# v1.net
KiCad netlist of a schematic drawn in EAGLE
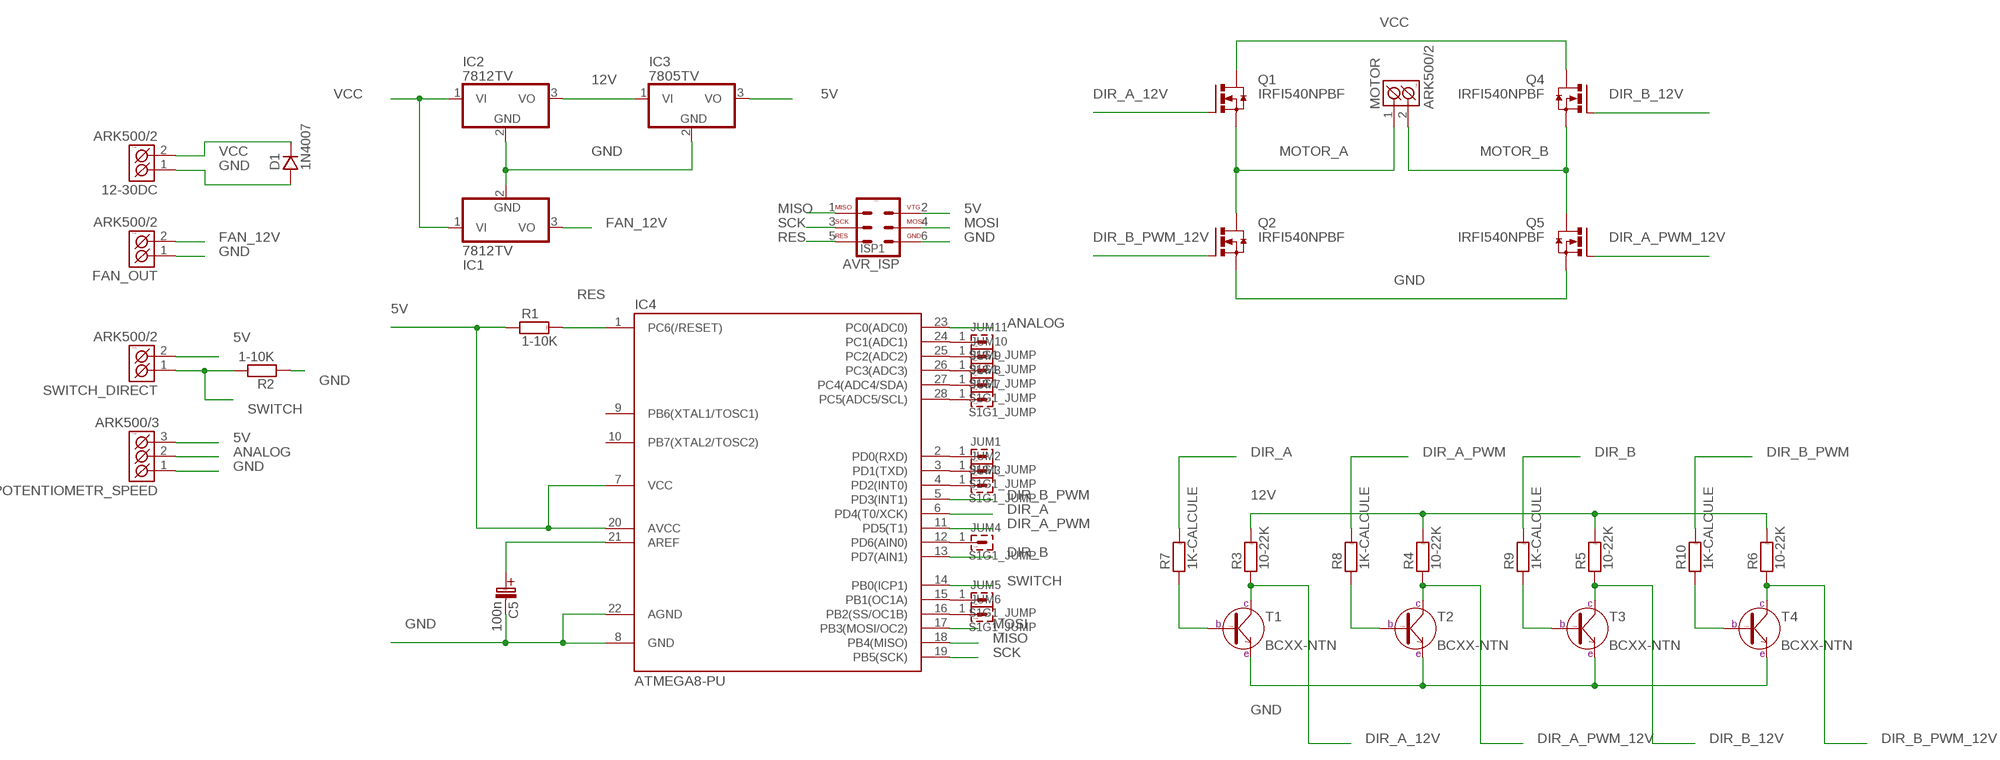
[diagram p0: schematic, sheet 1]

(export (version "E")
  (design (tool "Eeschema 10.0.6"))
  (components
    (comp (ref "12-30DC")
      (value "ARK500/2")
      (footprint "eagle-import:ARK500_2")
      (libsource (lib "eagle-import") (part "ARK500/2"))
    )
    (comp (ref "C5")
      (value "100n")
      (footprint "eagle-import:C-EL_2,5")
      (libsource (lib "eagle-import") (part "C-EL_2,5"))
    )
    (comp (ref "D1")
      (value "1N4007")
      (footprint "eagle-import:DO41")
      (libsource (lib "eagle-import") (part "1N4007"))
    )
    (comp (ref "FAN_OUT")
      (value "ARK500/2")
      (footprint "eagle-import:ARK500_2")
      (libsource (lib "eagle-import") (part "ARK500/2"))
    )
    (comp (ref "IC1")
      (value "7812TV")
      (footprint "eagle-import:TO220V")
      (libsource (lib "eagle-import") (part "78TV12"))
    )
    (comp (ref "IC2")
      (value "7812TV")
      (footprint "eagle-import:TO220V")
      (libsource (lib "eagle-import") (part "78TV12"))
    )
    (comp (ref "IC3")
      (value "7805TV")
      (footprint "eagle-import:TO220V")
      (libsource (lib "eagle-import") (part "78TV05"))
    )
    (comp (ref "IC4")
      (value "ATMEGA8-PU")
      (footprint "eagle-import:DIL28-3")
      (libsource (lib "eagle-import") (part "ATMEGA8-PU"))
    )
    (comp (ref "ISP1")
      (value "AVR_ISP")
      (footprint "eagle-import:MLW06G")
      (libsource (lib "eagle-import") (part "AVR_ISP"))
    )
    (comp (ref "JUM1")
      (value "S1G1_JUMP")
      (footprint "eagle-import:S1G1_JUM")
      (libsource (lib "eagle-import") (part "S1G1_JUMP"))
    )
    (comp (ref "JUM2")
      (value "S1G1_JUMP")
      (footprint "eagle-import:S1G1_JUM")
      (libsource (lib "eagle-import") (part "S1G1_JUMP"))
    )
    (comp (ref "JUM3")
      (value "S1G1_JUMP")
      (footprint "eagle-import:S1G1_JUM")
      (libsource (lib "eagle-import") (part "S1G1_JUMP"))
    )
    (comp (ref "JUM4")
      (value "S1G1_JUMP")
      (footprint "eagle-import:S1G1_JUM")
      (libsource (lib "eagle-import") (part "S1G1_JUMP"))
    )
    (comp (ref "JUM5")
      (value "S1G1_JUMP")
      (footprint "eagle-import:S1G1_JUM")
      (libsource (lib "eagle-import") (part "S1G1_JUMP"))
    )
    (comp (ref "JUM6")
      (value "S1G1_JUMP")
      (footprint "eagle-import:S1G1_JUM")
      (libsource (lib "eagle-import") (part "S1G1_JUMP"))
    )
    (comp (ref "JUM7")
      (value "S1G1_JUMP")
      (footprint "eagle-import:S1G1_JUM")
      (libsource (lib "eagle-import") (part "S1G1_JUMP"))
    )
    (comp (ref "JUM8")
      (value "S1G1_JUMP")
      (footprint "eagle-import:S1G1_JUM")
      (libsource (lib "eagle-import") (part "S1G1_JUMP"))
    )
    (comp (ref "JUM9")
      (value "S1G1_JUMP")
      (footprint "eagle-import:S1G1_JUM")
      (libsource (lib "eagle-import") (part "S1G1_JUMP"))
    )
    (comp (ref "JUM10")
      (value "S1G1_JUMP")
      (footprint "eagle-import:S1G1_JUM")
      (libsource (lib "eagle-import") (part "S1G1_JUMP"))
    )
    (comp (ref "JUM11")
      (value "S1G1_JUMP")
      (footprint "eagle-import:S1G1_JUM")
      (libsource (lib "eagle-import") (part "S1G1_JUMP"))
    )
    (comp (ref "MOTOR")
      (value "ARK500/2")
      (footprint "eagle-import:ARK500_2")
      (libsource (lib "eagle-import") (part "ARK500/2"))
    )
    (comp (ref "POTENTIOMETR_SPEED")
      (value "ARK500/3")
      (footprint "eagle-import:ARK500_3")
      (libsource (lib "eagle-import") (part "ARK500/3"))
    )
    (comp (ref "Q1")
      (value "IRFI540NPBF")
      (footprint "eagle-import:TO220BH")
      (libsource (lib "eagle-import") (part "IRFI540NPBF"))
    )
    (comp (ref "Q2")
      (value "IRFI540NPBF")
      (footprint "eagle-import:TO220BH")
      (libsource (lib "eagle-import") (part "IRFI540NPBF"))
    )
    (comp (ref "Q4")
      (value "IRFI540NPBF")
      (footprint "eagle-import:TO220BH")
      (libsource (lib "eagle-import") (part "IRFI540NPBF"))
    )
    (comp (ref "Q5")
      (value "IRFI540NPBF")
      (footprint "eagle-import:TO220BH")
      (libsource (lib "eagle-import") (part "IRFI540NPBF"))
    )
    (comp (ref "R1")
      (value "1-10K")
      (footprint "eagle-import:R-7,5")
      (libsource (lib "eagle-import") (part "R_7,5"))
    )
    (comp (ref "R2")
      (value "1-10K")
      (footprint "eagle-import:R-7,5")
      (libsource (lib "eagle-import") (part "R_7,5"))
    )
    (comp (ref "R3")
      (value "10-22K")
      (footprint "eagle-import:R-7,5")
      (libsource (lib "eagle-import") (part "R_7,5"))
    )
    (comp (ref "R4")
      (value "10-22K")
      (footprint "eagle-import:R-7,5")
      (libsource (lib "eagle-import") (part "R_7,5"))
    )
    (comp (ref "R5")
      (value "10-22K")
      (footprint "eagle-import:R-7,5")
      (libsource (lib "eagle-import") (part "R_7,5"))
    )
    (comp (ref "R6")
      (value "10-22K")
      (footprint "eagle-import:R-7,5")
      (libsource (lib "eagle-import") (part "R_7,5"))
    )
    (comp (ref "R7")
      (value "1K-CALCULE")
      (footprint "eagle-import:R-7,5")
      (libsource (lib "eagle-import") (part "R_7,5"))
    )
    (comp (ref "R8")
      (value "1K-CALCULE")
      (footprint "eagle-import:R-7,5")
      (libsource (lib "eagle-import") (part "R_7,5"))
    )
    (comp (ref "R9")
      (value "1K-CALCULE")
      (footprint "eagle-import:R-7,5")
      (libsource (lib "eagle-import") (part "R_7,5"))
    )
    (comp (ref "R10")
      (value "1K-CALCULE")
      (footprint "eagle-import:R-7,5")
      (libsource (lib "eagle-import") (part "R_7,5"))
    )
    (comp (ref "SWITCH_DIRECT")
      (value "ARK500/2")
      (footprint "eagle-import:ARK500_2")
      (libsource (lib "eagle-import") (part "ARK500/2"))
    )
    (comp (ref "T1")
      (value "BCXX-NTN")
      (footprint "eagle-import:TO-92")
      (libsource (lib "eagle-import") (part "BC546"))
    )
    (comp (ref "T2")
      (value "BCXX-NTN")
      (footprint "eagle-import:TO-92")
      (libsource (lib "eagle-import") (part "BC546"))
    )
    (comp (ref "T3")
      (value "BCXX-NTN")
      (footprint "eagle-import:TO-92")
      (libsource (lib "eagle-import") (part "BC546"))
    )
    (comp (ref "T4")
      (value "BCXX-NTN")
      (footprint "eagle-import:TO-92")
      (libsource (lib "eagle-import") (part "BC546"))
    )
  )
  (nets
    (net (code "1") (name "/5V") (class "Default")
      (node (ref "IC3") (pin "3") (pinfunction "VO_3") (pintype "passive"))
      (node (ref "IC4") (pin "20") (pinfunction "AVCC_20") (pintype "passive"))
      (node (ref "IC4") (pin "7") (pinfunction "VCC_7") (pintype "power_in"))
      (node (ref "ISP1") (pin "2") (pinfunction "2_2") (pintype "passive"))
      (node (ref "POTENTIOMETR_SPEED") (pin "3") (pinfunction "K3_3") (pintype "passive"))
      (node (ref "R1") (pin "1") (pinfunction "1_1") (pintype "passive"))
      (node (ref "SWITCH_DIRECT") (pin "2") (pinfunction "K2_2") (pintype "passive"))
    )
    (net (code "2") (name "/12V") (class "Default")
      (node (ref "IC2") (pin "3") (pinfunction "VO_3") (pintype "passive"))
      (node (ref "IC3") (pin "1") (pinfunction "VI_1") (pintype "input"))
      (node (ref "R3") (pin "2") (pinfunction "2_2") (pintype "passive"))
      (node (ref "R4") (pin "2") (pinfunction "2_2") (pintype "passive"))
      (node (ref "R5") (pin "2") (pinfunction "2_2") (pintype "passive"))
      (node (ref "R6") (pin "2") (pinfunction "2_2") (pintype "passive"))
    )
    (net (code "3") (name "/ANALOG") (class "Default")
      (node (ref "IC4") (pin "23") (pinfunction "PC0(ADC0)_23") (pintype "bidirectional"))
      (node (ref "POTENTIOMETR_SPEED") (pin "2") (pinfunction "K2_2") (pintype "passive"))
    )
    (net (code "4") (name "/DIR_A") (class "Default")
      (node (ref "IC4") (pin "6") (pinfunction "PD4(T0/XCK)_6") (pintype "bidirectional"))
      (node (ref "R7") (pin "2") (pinfunction "2_2") (pintype "passive"))
    )
    (net (code "5") (name "/DIR_A_12V") (class "Default")
      (node (ref "Q1") (pin "G") (pinfunction "G_G") (pintype "passive"))
      (node (ref "R3") (pin "1") (pinfunction "1_1") (pintype "passive"))
      (node (ref "T1") (pin "1") (pinfunction "C_1") (pintype "passive"))
    )
    (net (code "6") (name "/DIR_A_PWM") (class "Default")
      (node (ref "IC4") (pin "11") (pinfunction "PD5(T1)_11") (pintype "bidirectional"))
      (node (ref "R8") (pin "2") (pinfunction "2_2") (pintype "passive"))
    )
    (net (code "7") (name "/DIR_A_PWM_12V") (class "Default")
      (node (ref "Q5") (pin "G") (pinfunction "G_G") (pintype "passive"))
      (node (ref "R4") (pin "1") (pinfunction "1_1") (pintype "passive"))
      (node (ref "T2") (pin "1") (pinfunction "C_1") (pintype "passive"))
    )
    (net (code "8") (name "/DIR_B") (class "Default")
      (node (ref "IC4") (pin "13") (pinfunction "PD7(AIN1)_13") (pintype "bidirectional"))
      (node (ref "R9") (pin "2") (pinfunction "2_2") (pintype "passive"))
    )
    (net (code "9") (name "/DIR_B_12V") (class "Default")
      (node (ref "Q4") (pin "G") (pinfunction "G_G") (pintype "passive"))
      (node (ref "R5") (pin "1") (pinfunction "1_1") (pintype "passive"))
      (node (ref "T3") (pin "1") (pinfunction "C_1") (pintype "passive"))
    )
    (net (code "10") (name "/DIR_B_PWM") (class "Default")
      (node (ref "IC4") (pin "5") (pinfunction "PD3(INT1)_5") (pintype "bidirectional"))
      (node (ref "R10") (pin "2") (pinfunction "2_2") (pintype "passive"))
    )
    (net (code "11") (name "/DIR_B_PWM_12V") (class "Default")
      (node (ref "Q2") (pin "G") (pinfunction "G_G") (pintype "passive"))
      (node (ref "R6") (pin "1") (pinfunction "1_1") (pintype "passive"))
      (node (ref "T4") (pin "1") (pinfunction "C_1") (pintype "passive"))
    )
    (net (code "12") (name "/FAN_12V") (class "Default")
      (node (ref "FAN_OUT") (pin "2") (pinfunction "K2_2") (pintype "passive"))
      (node (ref "IC1") (pin "3") (pinfunction "VO_3") (pintype "passive"))
    )
    (net (code "13") (name "/GND") (class "Default")
      (node (ref "12-30DC") (pin "1") (pinfunction "K1_1") (pintype "passive"))
      (node (ref "C5") (pin "C-") (pinfunction "C_EL-_C-") (pintype "passive"))
      (node (ref "D1") (pin "A") (pinfunction "A_A") (pintype "passive"))
      (node (ref "FAN_OUT") (pin "1") (pinfunction "K1_1") (pintype "passive"))
      (node (ref "IC1") (pin "2") (pinfunction "GND_2") (pintype "passive"))
      (node (ref "IC2") (pin "2") (pinfunction "GND_2") (pintype "passive"))
      (node (ref "IC3") (pin "2") (pinfunction "GND_2") (pintype "passive"))
      (node (ref "IC4") (pin "22") (pinfunction "AGND_22") (pintype "power_in"))
      (node (ref "IC4") (pin "8") (pinfunction "GND_8") (pintype "power_in"))
      (node (ref "ISP1") (pin "6") (pinfunction "6_6") (pintype "passive"))
      (node (ref "POTENTIOMETR_SPEED") (pin "1") (pinfunction "K1_1") (pintype "passive"))
      (node (ref "Q2") (pin "S") (pinfunction "S_S") (pintype "passive"))
      (node (ref "Q5") (pin "S") (pinfunction "S_S") (pintype "passive"))
      (node (ref "R2") (pin "1") (pinfunction "1_1") (pintype "passive"))
      (node (ref "T1") (pin "3") (pinfunction "E_3") (pintype "passive"))
      (node (ref "T2") (pin "3") (pinfunction "E_3") (pintype "passive"))
      (node (ref "T3") (pin "3") (pinfunction "E_3") (pintype "passive"))
      (node (ref "T4") (pin "3") (pinfunction "E_3") (pintype "passive"))
    )
    (net (code "14") (name "/MISO") (class "Default")
      (node (ref "IC4") (pin "18") (pinfunction "PB4(MISO)_18") (pintype "bidirectional"))
      (node (ref "ISP1") (pin "1") (pinfunction "1_1") (pintype "passive"))
    )
    (net (code "15") (name "/MOSI") (class "Default")
      (node (ref "IC4") (pin "17") (pinfunction "PB3(MOSI/OC2)_17") (pintype "bidirectional"))
      (node (ref "ISP1") (pin "4") (pinfunction "4_4") (pintype "passive"))
    )
    (net (code "16") (name "/MOTOR_A") (class "Default")
      (node (ref "MOTOR") (pin "1") (pinfunction "K1_1") (pintype "passive"))
      (node (ref "Q1") (pin "S") (pinfunction "S_S") (pintype "passive"))
      (node (ref "Q2") (pin "D") (pinfunction "D_D") (pintype "passive"))
    )
    (net (code "17") (name "/MOTOR_B") (class "Default")
      (node (ref "MOTOR") (pin "2") (pinfunction "K2_2") (pintype "passive"))
      (node (ref "Q4") (pin "S") (pinfunction "S_S") (pintype "passive"))
      (node (ref "Q5") (pin "D") (pinfunction "D_D") (pintype "passive"))
    )
    (net (code "18") (name "/RES") (class "Default")
      (node (ref "IC4") (pin "1") (pinfunction "PC6(/RESET)_1") (pintype "bidirectional"))
      (node (ref "ISP1") (pin "5") (pinfunction "5_5") (pintype "passive"))
      (node (ref "R1") (pin "2") (pinfunction "2_2") (pintype "passive"))
    )
    (net (code "19") (name "/SCK") (class "Default")
      (node (ref "IC4") (pin "19") (pinfunction "PB5(SCK)_19") (pintype "bidirectional"))
      (node (ref "ISP1") (pin "3") (pinfunction "3_3") (pintype "passive"))
    )
    (net (code "20") (name "/SWITCH") (class "Default")
      (node (ref "IC4") (pin "14") (pinfunction "PB0(ICP1)_14") (pintype "bidirectional"))
      (node (ref "R2") (pin "2") (pinfunction "2_2") (pintype "passive"))
      (node (ref "SWITCH_DIRECT") (pin "1") (pinfunction "K1_1") (pintype "passive"))
    )
    (net (code "21") (name "/VCC") (class "Default")
      (node (ref "12-30DC") (pin "2") (pinfunction "K2_2") (pintype "passive"))
      (node (ref "D1") (pin "K") (pinfunction "K_K") (pintype "passive"))
      (node (ref "IC1") (pin "1") (pinfunction "VI_1") (pintype "input"))
      (node (ref "IC2") (pin "1") (pinfunction "VI_1") (pintype "input"))
      (node (ref "Q1") (pin "D") (pinfunction "D_D") (pintype "passive"))
      (node (ref "Q4") (pin "D") (pinfunction "D_D") (pintype "passive"))
    )
    (net (code "22") (name "Net-(C5-C_EL+)") (class "Default")
      (node (ref "C5") (pin "C+") (pinfunction "C_EL+_C+") (pintype "passive"))
      (node (ref "IC4") (pin "21") (pinfunction "AREF_21") (pintype "passive"))
    )
    (net (code "23") (name "Net-(IC4-PB1(OC1A))") (class "Default")
      (node (ref "IC4") (pin "15") (pinfunction "PB1(OC1A)_15") (pintype "bidirectional"))
      (node (ref "JUM5") (pin "1") (pinfunction "1_1") (pintype "passive"))
    )
    (net (code "24") (name "Net-(IC4-PB2(SS{slash}OC1B))") (class "Default")
      (node (ref "IC4") (pin "16") (pinfunction "PB2(SS/OC1B)_16") (pintype "bidirectional"))
      (node (ref "JUM6") (pin "1") (pinfunction "1_1") (pintype "passive"))
    )
    (net (code "25") (name "Net-(IC4-PC1(ADC1))") (class "Default")
      (node (ref "IC4") (pin "24") (pinfunction "PC1(ADC1)_24") (pintype "bidirectional"))
      (node (ref "JUM11") (pin "1") (pinfunction "1_1") (pintype "passive"))
    )
    (net (code "26") (name "Net-(IC4-PC2(ADC2))") (class "Default")
      (node (ref "IC4") (pin "25") (pinfunction "PC2(ADC2)_25") (pintype "bidirectional"))
      (node (ref "JUM10") (pin "1") (pinfunction "1_1") (pintype "passive"))
    )
    (net (code "27") (name "Net-(IC4-PC3(ADC3))") (class "Default")
      (node (ref "IC4") (pin "26") (pinfunction "PC3(ADC3)_26") (pintype "bidirectional"))
      (node (ref "JUM9") (pin "1") (pinfunction "1_1") (pintype "passive"))
    )
    (net (code "28") (name "Net-(IC4-PC4(ADC4{slash}SDA))") (class "Default")
      (node (ref "IC4") (pin "27") (pinfunction "PC4(ADC4/SDA)_27") (pintype "bidirectional"))
      (node (ref "JUM8") (pin "1") (pinfunction "1_1") (pintype "passive"))
    )
    (net (code "29") (name "Net-(IC4-PC5(ADC5{slash}SCL))") (class "Default")
      (node (ref "IC4") (pin "28") (pinfunction "PC5(ADC5/SCL)_28") (pintype "bidirectional"))
      (node (ref "JUM7") (pin "1") (pinfunction "1_1") (pintype "passive"))
    )
    (net (code "30") (name "Net-(IC4-PD0(RXD))") (class "Default")
      (node (ref "IC4") (pin "2") (pinfunction "PD0(RXD)_2") (pintype "bidirectional"))
      (node (ref "JUM1") (pin "1") (pinfunction "1_1") (pintype "passive"))
    )
    (net (code "31") (name "Net-(IC4-PD1(TXD))") (class "Default")
      (node (ref "IC4") (pin "3") (pinfunction "PD1(TXD)_3") (pintype "bidirectional"))
      (node (ref "JUM2") (pin "1") (pinfunction "1_1") (pintype "passive"))
    )
    (net (code "32") (name "Net-(IC4-PD2(INT0))") (class "Default")
      (node (ref "IC4") (pin "4") (pinfunction "PD2(INT0)_4") (pintype "bidirectional"))
      (node (ref "JUM3") (pin "1") (pinfunction "1_1") (pintype "passive"))
    )
    (net (code "33") (name "Net-(IC4-PD6(AIN0))") (class "Default")
      (node (ref "IC4") (pin "12") (pinfunction "PD6(AIN0)_12") (pintype "bidirectional"))
      (node (ref "JUM4") (pin "1") (pinfunction "1_1") (pintype "passive"))
    )
    (net (code "34") (name "Net-(T1-B)") (class "Default")
      (node (ref "R7") (pin "1") (pinfunction "1_1") (pintype "passive"))
      (node (ref "T1") (pin "2") (pinfunction "B_2") (pintype "passive"))
    )
    (net (code "35") (name "Net-(T2-B)") (class "Default")
      (node (ref "R8") (pin "1") (pinfunction "1_1") (pintype "passive"))
      (node (ref "T2") (pin "2") (pinfunction "B_2") (pintype "passive"))
    )
    (net (code "36") (name "Net-(T3-B)") (class "Default")
      (node (ref "R9") (pin "1") (pinfunction "1_1") (pintype "passive"))
      (node (ref "T3") (pin "2") (pinfunction "B_2") (pintype "passive"))
    )
    (net (code "37") (name "Net-(T4-B)") (class "Default")
      (node (ref "R10") (pin "1") (pinfunction "1_1") (pintype "passive"))
      (node (ref "T4") (pin "2") (pinfunction "B_2") (pintype "passive"))
    )
    (net (code "38") (name "unconnected-(IC4-PB6(XTAL1{slash}TOSC1)-Pad9)") (class "Default")
      (node (ref "IC4") (pin "9") (pinfunction "PB6(XTAL1/TOSC1)_9") (pintype "bidirectional"))
    )
    (net (code "39") (name "unconnected-(IC4-PB7(XTAL2{slash}TOSC2)-Pad10)") (class "Default")
      (node (ref "IC4") (pin "10") (pinfunction "PB7(XTAL2/TOSC2)_10") (pintype "bidirectional"))
    )
  )
)
